# USB_to_TTL.net
KiCad netlist of a schematic drawn in EAGLE
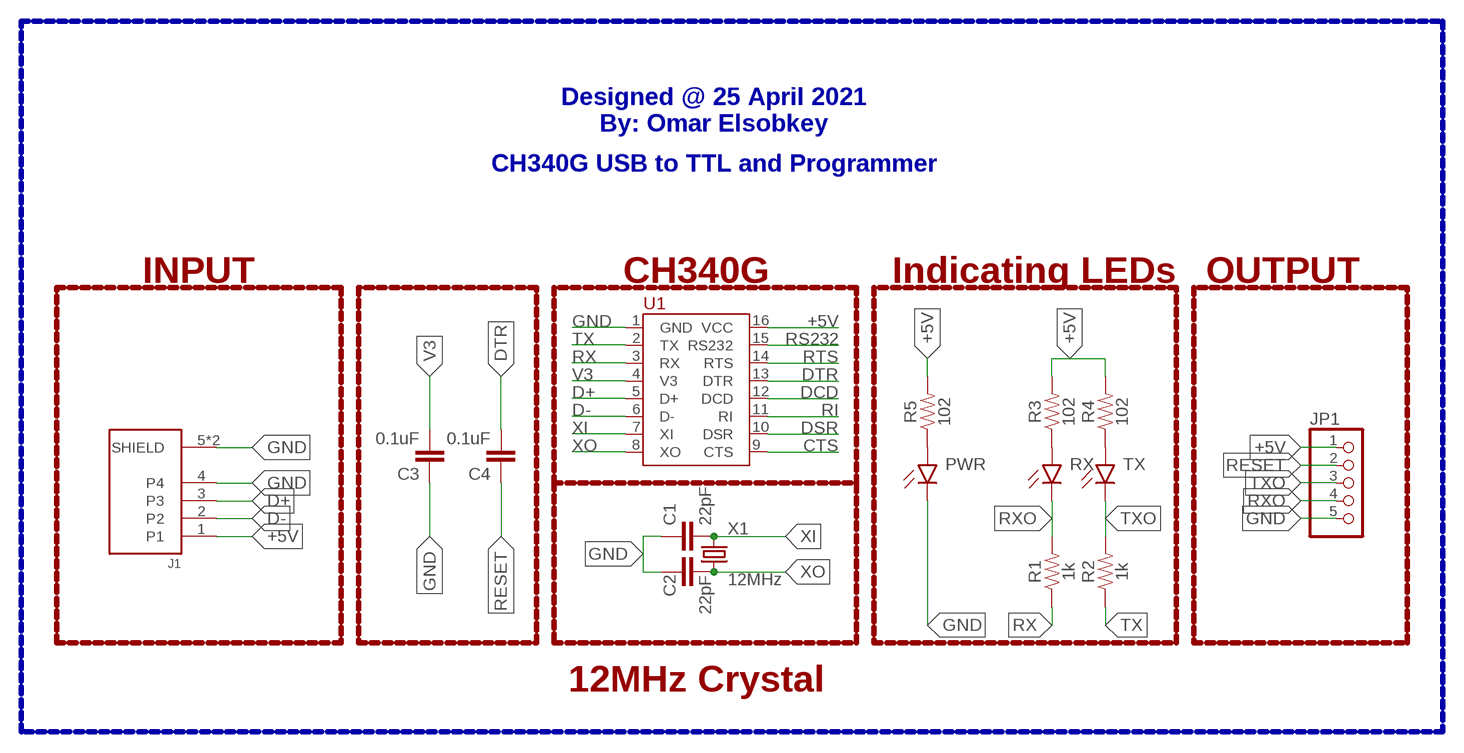
[diagram p0: schematic, sheet 1]

(export (version "E")
  (design (tool "Eeschema 10.0.6"))
  (components
    (comp (ref "C1")
      (value "22pF")
      (footprint "eagle-import:CAP-PTH-2.54")
      (libsource (lib "eagle-import") (part "22PF-PTH-2.54MM-200V-5%"))
    )
    (comp (ref "C2")
      (value "22pF")
      (footprint "eagle-import:CAP-PTH-2.54")
      (libsource (lib "eagle-import") (part "22PF-PTH-2.54MM-200V-5%"))
    )
    (comp (ref "C3")
      (value "0.1uF")
      (footprint "eagle-import:CAP-PTH-SMALL-KIT")
      (libsource (lib "eagle-import") (part "0.1UF-KIT-EZ-50V-20%"))
    )
    (comp (ref "C4")
      (value "0.1uF")
      (footprint "eagle-import:CAP-PTH-SMALL-KIT")
      (libsource (lib "eagle-import") (part "0.1UF-KIT-EZ-50V-20%"))
    )
    (comp (ref "J1")
      (value "0480371000")
      (footprint "eagle-import:0480371000")
      (fields
        (field (name "DIGIKEY_PART_NUMBER") "WM17118-ND")
        (field (name "MANUFACTURER") "Molex")
        (field (name "CREATED_BY") "PCBLayout.com")
      )
      (libsource (lib "eagle-import") (part "0480371000"))
    )
    (comp (ref "JP1")
      (value "PINHD-1X5/90")
      (footprint "eagle-import:1X05_90")
      (libsource (lib "eagle-import") (part "PINHD-1X5/90"))
    )
    (comp (ref "PWR")
      (value "CHIP-FLAT-B_0805")
      (footprint "eagle-import:LEDC2012X110N_FLAT-B")
      (libsource (lib "eagle-import") (part "CHIP-FLAT-B_0805"))
    )
    (comp (ref "R1")
      (value "1k")
      (footprint "eagle-import:1206")
      (libsource (lib "eagle-import") (part "RESISTOR1206"))
    )
    (comp (ref "R2")
      (value "1k")
      (footprint "eagle-import:1206")
      (libsource (lib "eagle-import") (part "RESISTOR1206"))
    )
    (comp (ref "R3")
      (value "102")
      (footprint "eagle-import:1206")
      (libsource (lib "eagle-import") (part "RESISTOR1206"))
    )
    (comp (ref "R4")
      (value "102")
      (footprint "eagle-import:1206")
      (libsource (lib "eagle-import") (part "RESISTOR1206"))
    )
    (comp (ref "R5")
      (value "102")
      (footprint "eagle-import:1206")
      (libsource (lib "eagle-import") (part "RESISTOR1206"))
    )
    (comp (ref "RX")
      (value "CHIP-FLAT-B_0805")
      (footprint "eagle-import:LEDC2012X110N_FLAT-B")
      (libsource (lib "eagle-import") (part "CHIP-FLAT-B_0805"))
    )
    (comp (ref "TX")
      (value "CHIP-FLAT-B_0805")
      (footprint "eagle-import:LEDC2012X110N_FLAT-B")
      (libsource (lib "eagle-import") (part "CHIP-FLAT-B_0805"))
    )
    (comp (ref "U1")
      (value "CH340G")
      (footprint "eagle-import:SOP-16")
      (libsource (lib "eagle-import") (part "CH340G"))
    )
    (comp (ref "X1")
      (value "12MHz")
      (footprint "eagle-import:XTAL_HC49")
      (fields
        (field (name "MANUFACTURER") "Xinhunjing ")
        (field (name "MPN") "49S/18PF")
        (field (name "CREATED_BY") "PCBLayout.com")
      )
      (libsource (lib "eagle-import") (part "49S/18PF"))
    )
  )
  (nets
    (net (code "1") (name "+5V") (class "Default")
      (node (ref "J1") (pin "1") (pinfunction "P1_1") (pintype "passive"))
      (node (ref "JP1") (pin "1") (pinfunction "1_1") (pintype "passive"))
      (node (ref "R3") (pin "2") (pinfunction "2_2") (pintype "passive"))
      (node (ref "R4") (pin "2") (pinfunction "2_2") (pintype "passive"))
      (node (ref "R5") (pin "2") (pinfunction "2_2") (pintype "passive"))
      (node (ref "U1") (pin "16") (pinfunction "VCC_16") (pintype "bidirectional"))
    )
    (net (code "2") (name "/CTS") (class "Default")
      (node (ref "U1") (pin "9") (pinfunction "CTS_9") (pintype "bidirectional"))
    )
    (net (code "3") (name "/DCD") (class "Default")
      (node (ref "U1") (pin "12") (pinfunction "DCD_12") (pintype "bidirectional"))
    )
    (net (code "4") (name "/DSR") (class "Default")
      (node (ref "U1") (pin "10") (pinfunction "DSR_10") (pintype "bidirectional"))
    )
    (net (code "5") (name "/RI") (class "Default")
      (node (ref "U1") (pin "11") (pinfunction "RI_11") (pintype "bidirectional"))
    )
    (net (code "6") (name "/RS232") (class "Default")
      (node (ref "U1") (pin "15") (pinfunction "RS232_15") (pintype "bidirectional"))
    )
    (net (code "7") (name "/RTS") (class "Default")
      (node (ref "U1") (pin "14") (pinfunction "RTS_14") (pintype "bidirectional"))
    )
    (net (code "8") (name "D+") (class "Default")
      (node (ref "J1") (pin "3") (pinfunction "P3_3") (pintype "passive"))
      (node (ref "U1") (pin "5") (pinfunction "D+_5") (pintype "bidirectional"))
    )
    (net (code "9") (name "D-") (class "Default")
      (node (ref "J1") (pin "2") (pinfunction "P2_2") (pintype "passive"))
      (node (ref "U1") (pin "6") (pinfunction "D-_6") (pintype "bidirectional"))
    )
    (net (code "10") (name "DTR") (class "Default")
      (node (ref "C4") (pin "2") (pinfunction "2_2") (pintype "passive"))
      (node (ref "U1") (pin "13") (pinfunction "DTR_13") (pintype "bidirectional"))
    )
    (net (code "11") (name "GND") (class "Default")
      (node (ref "C1") (pin "1") (pinfunction "1_1") (pintype "passive"))
      (node (ref "C2") (pin "1") (pinfunction "1_1") (pintype "passive"))
      (node (ref "C3") (pin "1") (pinfunction "1_1") (pintype "passive"))
      (node (ref "J1") (pin "4") (pinfunction "P4_4") (pintype "passive"))
      (node (ref "J1") (pin "5") (pinfunction "SHIELD_5") (pintype "passive"))
      (node (ref "J1") (pin "6") (pinfunction "SHIELD_6") (pintype "passive"))
      (node (ref "JP1") (pin "5") (pinfunction "5_5") (pintype "passive"))
      (node (ref "PWR") (pin "C") (pinfunction "C_C") (pintype "passive"))
      (node (ref "U1") (pin "1") (pinfunction "GND_1") (pintype "bidirectional"))
    )
    (net (code "12") (name "Net-(PWR-PadA)") (class "Default")
      (node (ref "PWR") (pin "A") (pinfunction "A_A") (pintype "passive"))
      (node (ref "R5") (pin "1") (pinfunction "1_1") (pintype "passive"))
    )
    (net (code "13") (name "Net-(R3-Pad1)") (class "Default")
      (node (ref "R3") (pin "1") (pinfunction "1_1") (pintype "passive"))
      (node (ref "RX") (pin "A") (pinfunction "A_A") (pintype "passive"))
    )
    (net (code "14") (name "Net-(R4-Pad1)") (class "Default")
      (node (ref "R4") (pin "1") (pinfunction "1_1") (pintype "passive"))
      (node (ref "TX") (pin "A") (pinfunction "A_A") (pintype "passive"))
    )
    (net (code "15") (name "RESET") (class "Default")
      (node (ref "C4") (pin "1") (pinfunction "1_1") (pintype "passive"))
      (node (ref "JP1") (pin "2") (pinfunction "2_2") (pintype "passive"))
    )
    (net (code "16") (name "RX") (class "Default")
      (node (ref "R1") (pin "1") (pinfunction "1_1") (pintype "passive"))
      (node (ref "U1") (pin "3") (pinfunction "RX_3") (pintype "bidirectional"))
    )
    (net (code "17") (name "RXO") (class "Default")
      (node (ref "JP1") (pin "4") (pinfunction "4_4") (pintype "passive"))
      (node (ref "R1") (pin "2") (pinfunction "2_2") (pintype "passive"))
      (node (ref "RX") (pin "C") (pinfunction "C_C") (pintype "passive"))
    )
    (net (code "18") (name "TX") (class "Default")
      (node (ref "R2") (pin "1") (pinfunction "1_1") (pintype "passive"))
      (node (ref "U1") (pin "2") (pinfunction "TX_2") (pintype "bidirectional"))
    )
    (net (code "19") (name "TXO") (class "Default")
      (node (ref "JP1") (pin "3") (pinfunction "3_3") (pintype "passive"))
      (node (ref "R2") (pin "2") (pinfunction "2_2") (pintype "passive"))
      (node (ref "TX") (pin "C") (pinfunction "C_C") (pintype "passive"))
    )
    (net (code "20") (name "V3") (class "Default")
      (node (ref "C3") (pin "2") (pinfunction "2_2") (pintype "passive"))
      (node (ref "U1") (pin "4") (pinfunction "V3_4") (pintype "bidirectional"))
    )
    (net (code "21") (name "XI") (class "Default")
      (node (ref "C1") (pin "2") (pinfunction "2_2") (pintype "passive"))
      (node (ref "U1") (pin "7") (pinfunction "XI_7") (pintype "bidirectional"))
      (node (ref "X1") (pin "2") (pinfunction "2_2") (pintype "passive"))
    )
    (net (code "22") (name "XO") (class "Default")
      (node (ref "C2") (pin "2") (pinfunction "2_2") (pintype "passive"))
      (node (ref "U1") (pin "8") (pinfunction "XO_8") (pintype "bidirectional"))
      (node (ref "X1") (pin "1") (pinfunction "1_1") (pintype "passive"))
    )
  )
)
